# node24-ethernet.net
KiCad netlist of a schematic drawn in Altium Designer
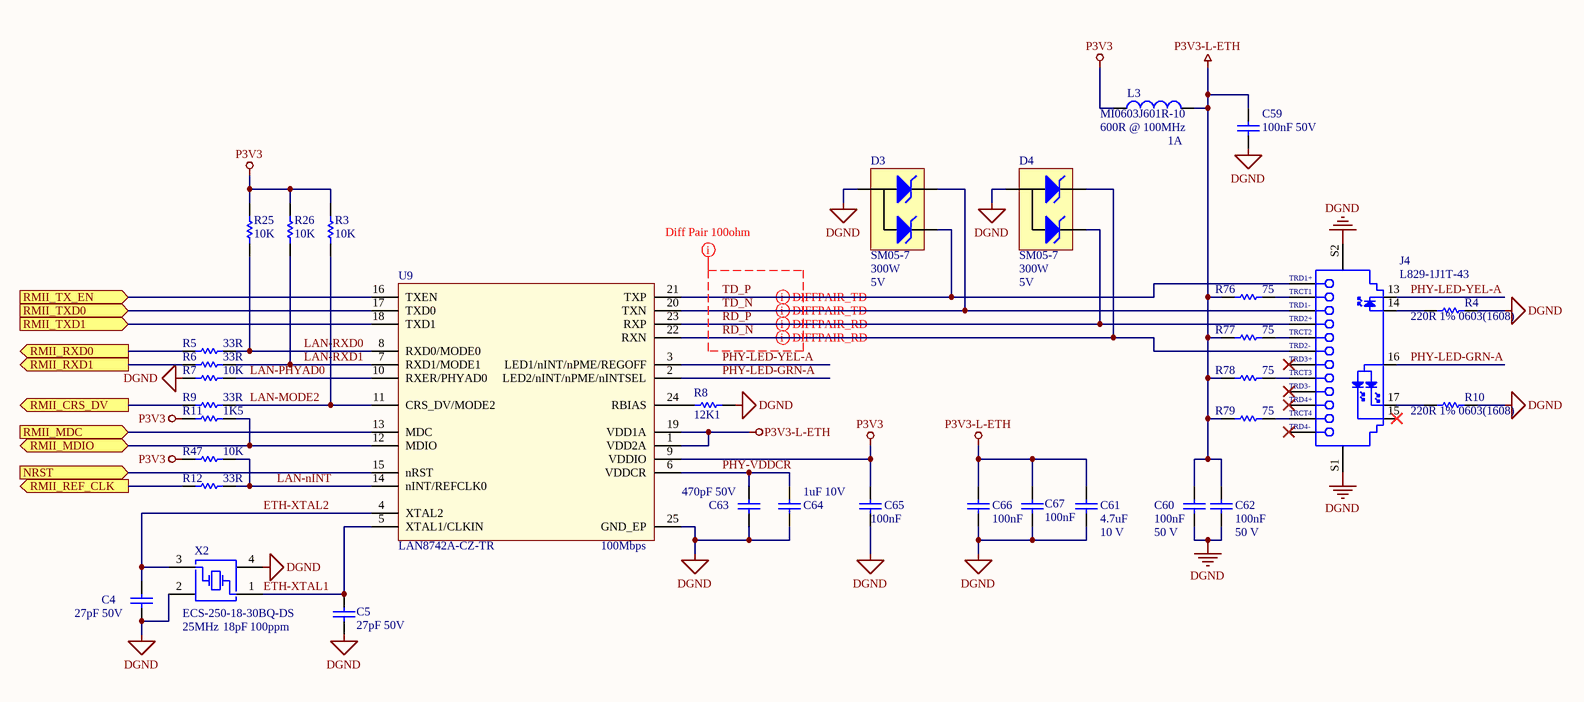
[diagram p0: node24-ethernet.SchDoc]

(export (version "E")
  (design (tool "Eeschema 10.0.6"))
  (components
    (comp (ref "C4")
      (value "27pF 50V")
      (footprint "CAPC0603(1608)100_L")
      (description "CAP 27pF 50V ±5% 0603 (1608 Metric) Thickness 1mm SMD")
      (fields (field (name "TOLERANCE") "Â±5%"))
      (libsource (lib "Altium Content Vault") (part "CAP"))
    )
    (comp (ref "C5")
      (value "27pF 50V")
      (footprint "CAPC0603(1608)100_L")
      (description "CAP 27pF 50V ±5% 0603 (1608 Metric) Thickness 1mm SMD")
      (fields (field (name "TOLERANCE") "Â±5%"))
      (libsource (lib "Altium Content Vault") (part "CAP"))
    )
    (comp (ref "C59")
      (value "100nF 50V")
      (footprint "CAPC0603(1608)100_L")
      (description "CAP 100nF 50V ±20% 0603 (1608 Metric) Thickness 1mm SMD")
      (fields (field (name "TOLERANCE") "Â±20%"))
      (libsource (lib "Altium Content Vault") (part "CAP"))
    )
    (comp (ref "C60")
      (value "100nF")
      (footprint "CAPC0603(1608)100_L")
      (description "CAP 100nF 50V ±20% 0603 (1608 Metric) Thickness 1mm SMD")
      (fields
        (field (name "TOLERANCE") "Â±20%")
        (field (name "RATED VOLTAGE") "50 V")
        (field (name "Comment") "100nF 50V")
      )
      (libsource (lib "Altium Content Vault") (part "CAP"))
    )
    (comp (ref "C61")
      (value "4.7uF")
      (footprint "CAPC0603(1608)100_L")
      (description "CAP 4.7uF 10V ±20% 0603 (1608 Metric) Thickness 1mm SMD")
      (fields
        (field (name "TOLERANCE") "Â±20%")
        (field (name "RATED VOLTAGE") "10 V")
        (field (name "Comment") "4.7uF 10V")
      )
      (libsource (lib "Altium Content Vault") (part "CAP"))
    )
    (comp (ref "C62")
      (value "100nF")
      (footprint "CAPC0603(1608)100_L")
      (description "CAP 100nF 50V ±20% 0603 (1608 Metric) Thickness 1mm SMD")
      (fields
        (field (name "TOLERANCE") "Â±20%")
        (field (name "RATED VOLTAGE") "50 V")
        (field (name "Comment") "100nF 50V")
      )
      (libsource (lib "Altium Content Vault") (part "CAP"))
    )
    (comp (ref "C63")
      (value "470pF 50V")
      (footprint "CAPC0603(1608)100_L")
      (description "CAP 470pF 50V ±20% 0603 (1608 Metric) Thickness 1mm SMD")
      (fields (field (name "TOLERANCE") "Â±20%"))
      (libsource (lib "Altium Content Vault") (part "CAP"))
    )
    (comp (ref "C64")
      (value "1uF 10V")
      (footprint "CAPC0603(1608)100_L")
      (description "CAP 1uF 10V ±20% 0603 (1608 Metric) Thickness 1mm SMD")
      (fields (field (name "TOLERANCE") "Â±20%"))
      (libsource (lib "Altium Content Vault") (part "CAP"))
    )
    (comp (ref "C65")
      (value "100nF")
      (footprint "CAPC0603(1608)100_L")
      (description "CAP 100nF 50V ±20% 0603 (1608 Metric) Thickness 1mm SMD")
      (fields (field (name "TOLERANCE") "Â±20%"))
      (libsource (lib "Altium Content Vault") (part "CAP"))
    )
    (comp (ref "C66")
      (value "100nF")
      (footprint "CAPC0603(1608)100_L")
      (description "CAP 100nF 50V ±20% 0603 (1608 Metric) Thickness 1mm SMD")
      (fields (field (name "TOLERANCE") "Â±20%"))
      (libsource (lib "Altium Content Vault") (part "CAP"))
    )
    (comp (ref "C67")
      (value "100nF")
      (footprint "CAPC0603(1608)100_L")
      (description "CAP 100nF 50V ±20% 0603 (1608 Metric) Thickness 1mm SMD")
      (fields (field (name "TOLERANCE") "Â±20%"))
      (libsource (lib "Altium Content Vault") (part "CAP"))
    )
    (comp (ref "D3")
      (value "TVS_5V_DUAL_SOT23-3_SM05-7")
      (footprint "SOT-23")
      (description "TVS DIODE 5VWM 20.6VC SOT23")
      (fields
        (field (name "MANUFACTURER") "Diodes")
        (field (name "MANUFACTURER PART NUMBER") "SM05-7")
        (field (name "MAX POWER DISSIPATION") "300W")
        (field (name "REVERSE STANDOFF VOLTAGE") "5V")
      )
      (libsource (lib "node") (part "TVS_5V_DUAL_SOT23-3_SM05-7"))
    )
    (comp (ref "D4")
      (value "TVS_5V_DUAL_SOT23-3_SM05-7")
      (footprint "SOT-23")
      (description "TVS DIODE 5VWM 20.6VC SOT23")
      (fields
        (field (name "MANUFACTURER") "Diodes")
        (field (name "MANUFACTURER PART NUMBER") "SM05-7")
        (field (name "MAX POWER DISSIPATION") "300W")
        (field (name "REVERSE STANDOFF VOLTAGE") "5V")
      )
      (libsource (lib "node") (part "TVS_5V_DUAL_SOT23-3_SM05-7"))
    )
    (comp (ref "J4")
      (value "L829-1J1T-43")
      (footprint "BELS-L829-1J1T-43_V")
      (description "Gigabit MagJack(R) Ultra Low Profile, 10/100/1000 Base-T, 19-Pin THD, RoHS, Tray")
      (libsource (lib "Altium Content Vault") (part "RJ45-17-2SHLD"))
    )
    (comp (ref "L3")
      (value "BEAD_LAIRD_MI0603J601R-10")
      (footprint "0603L")
      (description "FERRITE BEAD 600 OHM 0603")
      (fields
        (field (name "MANUFACTURER") "Laird")
        (field (name "MANUFACTURER PART NUMBER") "MI0603J601R-10")
        (field (name "MAX DC CURRENT") "1A")
        (field (name "IMPEDANCE") "600R @ 100MHz")
      )
      (libsource (lib "node") (part "BEAD_LAIRD_MI0603J601R-10"))
    )
    (comp (ref "R3")
      (value "10K")
      (footprint "RESC0603(1608)_L")
      (description "10K 0.1W 1% 0603 (1608 Metric)  SMD")
      (fields (field (name "POWER") "0.1 W") (field (name "TOLERANCE") "1 %"))
      (libsource (lib "Altium Content Vault") (part "RES"))
    )
    (comp (ref "R4")
      (value "220R 1% 0603(1608)")
      (footprint "RESC0603(1608)_L")
      (description "220R 0.1W 1% 0603 (1608 Metric)  SMD")
      (fields (field (name "TOLERANCE") "1 %") (field (name "POWER") "0.1 W"))
      (libsource (lib "Altium Content Vault") (part "RES"))
    )
    (comp (ref "R5")
      (value "33R")
      (footprint "RESC0603(1608)_L")
      (description "33R 0.1W 1% 0603 (1608 Metric)  SMD")
      (fields (field (name "TOLERANCE") "1 %") (field (name "POWER") "0.1 W"))
      (libsource (lib "Altium Content Vault") (part "RES"))
    )
    (comp (ref "R6")
      (value "33R")
      (footprint "RESC0603(1608)_L")
      (description "33R 0.1W 1% 0603 (1608 Metric)  SMD")
      (fields (field (name "TOLERANCE") "1 %") (field (name "POWER") "0.1 W"))
      (libsource (lib "Altium Content Vault") (part "RES"))
    )
    (comp (ref "R7")
      (value "10K")
      (footprint "RESC0603(1608)_L")
      (description "10K 0.1W 1% 0603 (1608 Metric)  SMD")
      (fields (field (name "POWER") "0.1 W") (field (name "TOLERANCE") "1 %"))
      (libsource (lib "Altium Content Vault") (part "RES"))
    )
    (comp (ref "R8")
      (value "12K1")
      (footprint "RESC0603(1608)_L")
      (description "12K1 0.1W 1% 0603 (1608 Metric)  SMD")
      (fields (field (name "POWER") "0.1 W") (field (name "TOLERANCE") "1 %"))
      (libsource (lib "Altium Content Vault") (part "RES"))
    )
    (comp (ref "R9")
      (value "33R")
      (footprint "RESC0603(1608)_L")
      (description "33R 0.1W 1% 0603 (1608 Metric)  SMD")
      (fields (field (name "TOLERANCE") "1 %") (field (name "POWER") "0.1 W"))
      (libsource (lib "Altium Content Vault") (part "RES"))
    )
    (comp (ref "R10")
      (value "220R 1% 0603(1608)")
      (footprint "RESC0603(1608)_L")
      (description "220R 0.1W 1% 0603 (1608 Metric)  SMD")
      (fields (field (name "TOLERANCE") "1 %") (field (name "POWER") "0.1 W"))
      (libsource (lib "Altium Content Vault") (part "RES"))
    )
    (comp (ref "R11")
      (value "1K5")
      (footprint "RESC0603(1608)_L")
      (description "1K5 0.1W 1% 0603 (1608 Metric)  SMD")
      (fields (field (name "POWER") "0.1 W") (field (name "TOLERANCE") "1 %"))
      (libsource (lib "Altium Content Vault") (part "RES"))
    )
    (comp (ref "R12")
      (value "33R")
      (footprint "RESC0603(1608)_L")
      (description "33R 0.1W 1% 0603 (1608 Metric)  SMD")
      (fields (field (name "TOLERANCE") "1 %") (field (name "POWER") "0.1 W"))
      (libsource (lib "Altium Content Vault") (part "RES"))
    )
    (comp (ref "R25")
      (value "10K")
      (footprint "RESC0603(1608)_L")
      (description "10K 0.1W 1% 0603 (1608 Metric)  SMD")
      (fields (field (name "POWER") "0.1 W") (field (name "TOLERANCE") "1 %"))
      (libsource (lib "Altium Content Vault") (part "RES"))
    )
    (comp (ref "R26")
      (value "10K")
      (footprint "RESC0603(1608)_L")
      (description "10K 0.1W 1% 0603 (1608 Metric)  SMD")
      (fields (field (name "POWER") "0.1 W") (field (name "TOLERANCE") "1 %"))
      (libsource (lib "Altium Content Vault") (part "RES"))
    )
    (comp (ref "R47")
      (value "10K")
      (footprint "RESC0603(1608)_L")
      (description "10K 0.1W 1% 0603 (1608 Metric)  SMD")
      (fields (field (name "POWER") "0.1 W") (field (name "TOLERANCE") "1 %"))
      (libsource (lib "Altium Content Vault") (part "RES"))
    )
    (comp (ref "R76")
      (value "75")
      (footprint "RESC0603(1608)_M")
      (description "75R 0.1W 1% 0603 (1608 Metric)  SMD")
      (fields (field (name "POWER") "0.1 W") (field (name "TOLERANCE") "1 %"))
      (libsource (lib "Altium Content Vault") (part "RES"))
    )
    (comp (ref "R77")
      (value "75")
      (footprint "RESC0603(1608)_M")
      (description "75R 0.1W 1% 0603 (1608 Metric)  SMD")
      (fields (field (name "POWER") "0.1 W") (field (name "TOLERANCE") "1 %"))
      (libsource (lib "Altium Content Vault") (part "RES"))
    )
    (comp (ref "R78")
      (value "75")
      (footprint "RESC0603(1608)_M")
      (description "75R 0.1W 1% 0603 (1608 Metric)  SMD")
      (fields (field (name "POWER") "0.1 W") (field (name "TOLERANCE") "1 %"))
      (libsource (lib "Altium Content Vault") (part "RES"))
    )
    (comp (ref "R79")
      (value "75")
      (footprint "RESC0603(1608)_M")
      (description "75R 0.1W 1% 0603 (1608 Metric)  SMD")
      (fields (field (name "POWER") "0.1 W") (field (name "TOLERANCE") "1 %"))
      (libsource (lib "Altium Content Vault") (part "RES"))
    )
    (comp (ref "U9")
      (value "LAN8742A-CZ-TR")
      (footprint "QFN24_B4X4_P0MM5_EP")
      (fields
        (field (name "MANUFACTURER") "Microchip")
        (field (name "DATA RATE") "100Mbps")
        (field (name "MANUFACTURER PART NUMBER") "LAN8742A-CZ-TR")
      )
      (libsource (lib "node") (part "IC_INTERFACE_ETHERNET_PHY_LAN8742A-CZ-TR"))
    )
    (comp (ref "X2")
      (value "XTAL_25MHz_18PF_4SMD_100PPM_AUTOMOTIVE_ECS-250-18-30BQ-DS")
      (footprint "XTAL_4SMD_5x3mm2")
      (description "Crystals 25.000MHz 18pF 100ppm -40 to 125C")
      (fields
        (field (name "MANUFACTURER") "ECS International")
        (field (name "TOLERANCE") "30ppm")
        (field (name "LOAD CAPACITANCE") "18pF")
        (field (name "FREQUENCY STABILITY") "100ppm")
        (field (name "FREQUENCY") "25MHz")
        (field (name "MANUFACTURER PART NUMBER") "ECS-250-18-30BQ-DS")
      )
      (libsource (lib "node") (part "XTAL_25MHz_18PF_4SMD_100PPM_AUTOMOTIVE_ECS-250-18-30BQ-DS"))
    )
  )
  (nets
    (net (code "1") (name "/ETH-XTAL1") (class "Default")
      (node (ref "C5") (pin "1") (pinfunction "1_1") (pintype "passive"))
      (node (ref "U9") (pin "5") (pinfunction "XTAL1/CLKIN_5") (pintype "passive"))
      (node (ref "X2") (pin "1") (pinfunction "OSC1_1") (pintype "passive"))
    )
    (net (code "2") (name "/ETH-XTAL2") (class "Default")
      (node (ref "C4") (pin "1") (pinfunction "1_1") (pintype "passive"))
      (node (ref "U9") (pin "4") (pinfunction "XTAL2_4") (pintype "passive"))
      (node (ref "X2") (pin "3") (pinfunction "3_3") (pintype "passive"))
    )
    (net (code "3") (name "/LAN-MODE2") (class "Default")
      (node (ref "R3") (pin "1") (pinfunction "1_1") (pintype "passive"))
      (node (ref "R9") (pin "2") (pinfunction "2_2") (pintype "passive"))
      (node (ref "U9") (pin "11") (pinfunction "CRS_DV/MODE2_11") (pintype "passive"))
    )
    (net (code "4") (name "/LAN-PHYAD0") (class "Default")
      (node (ref "R7") (pin "1") (pinfunction "1_1") (pintype "passive"))
      (node (ref "U9") (pin "10") (pinfunction "RXER/PHYAD0_10") (pintype "passive"))
    )
    (net (code "5") (name "/LAN-RXD0") (class "Default")
      (node (ref "R25") (pin "1") (pinfunction "1_1") (pintype "passive"))
      (node (ref "R5") (pin "2") (pinfunction "2_2") (pintype "passive"))
      (node (ref "U9") (pin "8") (pinfunction "RXD0/MODE0_8") (pintype "passive"))
    )
    (net (code "6") (name "/LAN-RXD1") (class "Default")
      (node (ref "R26") (pin "1") (pinfunction "1_1") (pintype "passive"))
      (node (ref "R6") (pin "2") (pinfunction "2_2") (pintype "passive"))
      (node (ref "U9") (pin "7") (pinfunction "RXD1/MODE1_7") (pintype "passive"))
    )
    (net (code "7") (name "/LAN-nINT") (class "Default")
      (node (ref "R12") (pin "2") (pinfunction "2_2") (pintype "passive"))
      (node (ref "R47") (pin "1") (pinfunction "1_1") (pintype "passive"))
      (node (ref "U9") (pin "14") (pinfunction "nINT/REFCLK0_14") (pintype "passive"))
    )
    (net (code "8") (name "/NRST") (class "Default")
      (node (ref "U9") (pin "15") (pinfunction "nRST_15") (pintype "passive"))
    )
    (net (code "9") (name "/PHY-LED-GRN-A") (class "Default")
      (node (ref "J4") (pin "16") (pinfunction "16_16") (pintype "passive"))
      (node (ref "U9") (pin "2") (pinfunction "LED2/nINT/nPME/nINTSEL_2") (pintype "passive"))
    )
    (net (code "10") (name "/PHY-LED-YEL-A") (class "Default")
      (node (ref "J4") (pin "13") (pinfunction "13_13") (pintype "passive"))
      (node (ref "U9") (pin "3") (pinfunction "LED1/nINT/nPME/REGOFF_3") (pintype "passive"))
    )
    (net (code "11") (name "/PHY-VDDCR") (class "Default")
      (node (ref "C63") (pin "2") (pinfunction "2_2") (pintype "passive"))
      (node (ref "C64") (pin "2") (pinfunction "2_2") (pintype "passive"))
      (node (ref "U9") (pin "6") (pinfunction "VDDCR_6") (pintype "passive"))
    )
    (net (code "12") (name "/RD_N") (class "Default")
      (node (ref "D4") (pin "1") (pinfunction "K1_1") (pintype "passive"))
      (node (ref "J4") (pin "6") (pinfunction "TRD2-_6") (pintype "passive"))
      (node (ref "U9") (pin "22") (pinfunction "RXN_22") (pintype "passive"))
    )
    (net (code "13") (name "/RD_P") (class "Default")
      (node (ref "D4") (pin "2") (pinfunction "K2_2") (pintype "passive"))
      (node (ref "J4") (pin "4") (pinfunction "TRD2+_4") (pintype "passive"))
      (node (ref "U9") (pin "23") (pinfunction "RXP_23") (pintype "passive"))
    )
    (net (code "14") (name "/RMII_CRS_DV") (class "Default")
      (node (ref "R9") (pin "1") (pinfunction "1_1") (pintype "passive"))
    )
    (net (code "15") (name "/RMII_MDC") (class "Default")
      (node (ref "U9") (pin "13") (pinfunction "MDC_13") (pintype "passive"))
    )
    (net (code "16") (name "/RMII_MDIO") (class "Default")
      (node (ref "R11") (pin "2") (pinfunction "2_2") (pintype "passive"))
      (node (ref "U9") (pin "12") (pinfunction "MDIO_12") (pintype "passive"))
    )
    (net (code "17") (name "/RMII_REF_CLK") (class "Default")
      (node (ref "R12") (pin "1") (pinfunction "1_1") (pintype "passive"))
    )
    (net (code "18") (name "/RMII_RXD0") (class "Default")
      (node (ref "R5") (pin "1") (pinfunction "1_1") (pintype "passive"))
    )
    (net (code "19") (name "/RMII_RXD1") (class "Default")
      (node (ref "R6") (pin "1") (pinfunction "1_1") (pintype "passive"))
    )
    (net (code "20") (name "/RMII_TXD0") (class "Default")
      (node (ref "U9") (pin "17") (pinfunction "TXD0_17") (pintype "passive"))
    )
    (net (code "21") (name "/RMII_TXD1") (class "Default")
      (node (ref "U9") (pin "18") (pinfunction "TXD1_18") (pintype "passive"))
    )
    (net (code "22") (name "/RMII_TX_EN") (class "Default")
      (node (ref "U9") (pin "16") (pinfunction "TXEN_16") (pintype "passive"))
    )
    (net (code "23") (name "/TD_N") (class "Default")
      (node (ref "D3") (pin "1") (pinfunction "K1_1") (pintype "passive"))
      (node (ref "J4") (pin "3") (pinfunction "TRD1-_3") (pintype "passive"))
      (node (ref "U9") (pin "20") (pinfunction "TXN_20") (pintype "passive"))
    )
    (net (code "24") (name "/TD_P") (class "Default")
      (node (ref "D3") (pin "2") (pinfunction "K2_2") (pintype "passive"))
      (node (ref "J4") (pin "1") (pinfunction "TRD1+_1") (pintype "passive"))
      (node (ref "U9") (pin "21") (pinfunction "TXP_21") (pintype "passive"))
    )
    (net (code "25") (name "DGND") (class "Default")
      (node (ref "C4") (pin "2") (pinfunction "2_2") (pintype "passive"))
      (node (ref "C5") (pin "2") (pinfunction "2_2") (pintype "passive"))
      (node (ref "C59") (pin "1") (pinfunction "1_1") (pintype "passive"))
      (node (ref "C60") (pin "1") (pinfunction "1_1") (pintype "passive"))
      (node (ref "C61") (pin "2") (pinfunction "2_2") (pintype "passive"))
      (node (ref "C62") (pin "1") (pinfunction "1_1") (pintype "passive"))
      (node (ref "C63") (pin "1") (pinfunction "1_1") (pintype "passive"))
      (node (ref "C64") (pin "1") (pinfunction "1_1") (pintype "passive"))
      (node (ref "C65") (pin "1") (pinfunction "1_1") (pintype "passive"))
      (node (ref "C66") (pin "1") (pinfunction "1_1") (pintype "passive"))
      (node (ref "C67") (pin "1") (pinfunction "1_1") (pintype "passive"))
      (node (ref "D3") (pin "3") (pinfunction "A_3") (pintype "passive"))
      (node (ref "D4") (pin "3") (pinfunction "A_3") (pintype "passive"))
      (node (ref "J4") (pin "S1") (pinfunction "S1_S1") (pintype "passive"))
      (node (ref "J4") (pin "S2") (pinfunction "S2_S2") (pintype "passive"))
      (node (ref "R10") (pin "1") (pinfunction "1_1") (pintype "passive"))
      (node (ref "R4") (pin "1") (pinfunction "1_1") (pintype "passive"))
      (node (ref "R7") (pin "2") (pinfunction "2_2") (pintype "passive"))
      (node (ref "R8") (pin "2") (pinfunction "2_2") (pintype "passive"))
      (node (ref "U9") (pin "25") (pinfunction "GND_EP_25") (pintype "passive"))
      (node (ref "X2") (pin "2") (pinfunction "CAN_2") (pintype "passive"))
      (node (ref "X2") (pin "4") (pinfunction "CAN_4") (pintype "passive"))
    )
    (net (code "26") (name "Net-(J4-Pad14)") (class "Default")
      (node (ref "J4") (pin "14") (pinfunction "14_14") (pintype "passive"))
      (node (ref "R4") (pin "2") (pinfunction "2_2") (pintype "passive"))
    )
    (net (code "27") (name "Net-(J4-Pad17)") (class "Default")
      (node (ref "J4") (pin "17") (pinfunction "17_17") (pintype "passive"))
      (node (ref "R10") (pin "2") (pinfunction "2_2") (pintype "passive"))
    )
    (net (code "28") (name "Net-(J4-TRCT1)") (class "Default")
      (node (ref "J4") (pin "2") (pinfunction "TRCT1_2") (pintype "passive"))
      (node (ref "R76") (pin "2") (pinfunction "2_2") (pintype "passive"))
    )
    (net (code "29") (name "Net-(J4-TRCT2)") (class "Default")
      (node (ref "J4") (pin "5") (pinfunction "TRCT2_5") (pintype "passive"))
      (node (ref "R77") (pin "2") (pinfunction "2_2") (pintype "passive"))
    )
    (net (code "30") (name "Net-(J4-TRCT3)") (class "Default")
      (node (ref "J4") (pin "8") (pinfunction "TRCT3_8") (pintype "passive"))
      (node (ref "R78") (pin "2") (pinfunction "2_2") (pintype "passive"))
    )
    (net (code "31") (name "Net-(J4-TRCT4)") (class "Default")
      (node (ref "J4") (pin "11") (pinfunction "TRCT4_11") (pintype "passive"))
      (node (ref "R79") (pin "2") (pinfunction "2_2") (pintype "passive"))
    )
    (net (code "32") (name "Net-(U9-RBIAS)") (class "Default")
      (node (ref "R8") (pin "1") (pinfunction "1_1") (pintype "passive"))
      (node (ref "U9") (pin "24") (pinfunction "RBIAS_24") (pintype "passive"))
    )
    (net (code "33") (name "P3V3") (class "Default")
      (node (ref "C65") (pin "2") (pinfunction "2_2") (pintype "passive"))
      (node (ref "L3") (pin "1") (pinfunction "1_1") (pintype "passive"))
      (node (ref "R11") (pin "1") (pinfunction "1_1") (pintype "passive"))
      (node (ref "R25") (pin "2") (pinfunction "2_2") (pintype "passive"))
      (node (ref "R26") (pin "2") (pinfunction "2_2") (pintype "passive"))
      (node (ref "R3") (pin "2") (pinfunction "2_2") (pintype "passive"))
      (node (ref "R47") (pin "2") (pinfunction "2_2") (pintype "passive"))
      (node (ref "U9") (pin "9") (pinfunction "VDDIO_9") (pintype "passive"))
    )
    (net (code "34") (name "P3V3-L-ETH") (class "Default")
      (node (ref "C59") (pin "2") (pinfunction "2_2") (pintype "passive"))
      (node (ref "C60") (pin "2") (pinfunction "2_2") (pintype "passive"))
      (node (ref "C61") (pin "1") (pinfunction "1_1") (pintype "passive"))
      (node (ref "C62") (pin "2") (pinfunction "2_2") (pintype "passive"))
      (node (ref "C66") (pin "2") (pinfunction "2_2") (pintype "passive"))
      (node (ref "C67") (pin "2") (pinfunction "2_2") (pintype "passive"))
      (node (ref "L3") (pin "2") (pinfunction "2_2") (pintype "passive"))
      (node (ref "R76") (pin "1") (pinfunction "1_1") (pintype "passive"))
      (node (ref "R77") (pin "1") (pinfunction "1_1") (pintype "passive"))
      (node (ref "R78") (pin "1") (pinfunction "1_1") (pintype "passive"))
      (node (ref "R79") (pin "1") (pinfunction "1_1") (pintype "passive"))
      (node (ref "U9") (pin "1") (pinfunction "VDD2A_1") (pintype "passive"))
      (node (ref "U9") (pin "19") (pinfunction "VDD1A_19") (pintype "passive"))
    )
    (net (code "35") (name "unconnected-(J4-Pad15)") (class "Default")
      (node (ref "J4") (pin "15") (pinfunction "15_15") (pintype "passive+no_connect"))
    )
    (net (code "36") (name "unconnected-(J4-TRD3+-Pad7)") (class "Default")
      (node (ref "J4") (pin "7") (pinfunction "TRD3+_7") (pintype "passive+no_connect"))
    )
    (net (code "37") (name "unconnected-(J4-TRD3--Pad9)") (class "Default")
      (node (ref "J4") (pin "9") (pinfunction "TRD3-_9") (pintype "passive+no_connect"))
    )
    (net (code "38") (name "unconnected-(J4-TRD4+-Pad10)") (class "Default")
      (node (ref "J4") (pin "10") (pinfunction "TRD4+_10") (pintype "passive+no_connect"))
    )
    (net (code "39") (name "unconnected-(J4-TRD4--Pad12)") (class "Default")
      (node (ref "J4") (pin "12") (pinfunction "TRD4-_12") (pintype "passive+no_connect"))
    )
  )
)
